# Camera.net
KiCad netlist of a schematic drawn in Altium Designer
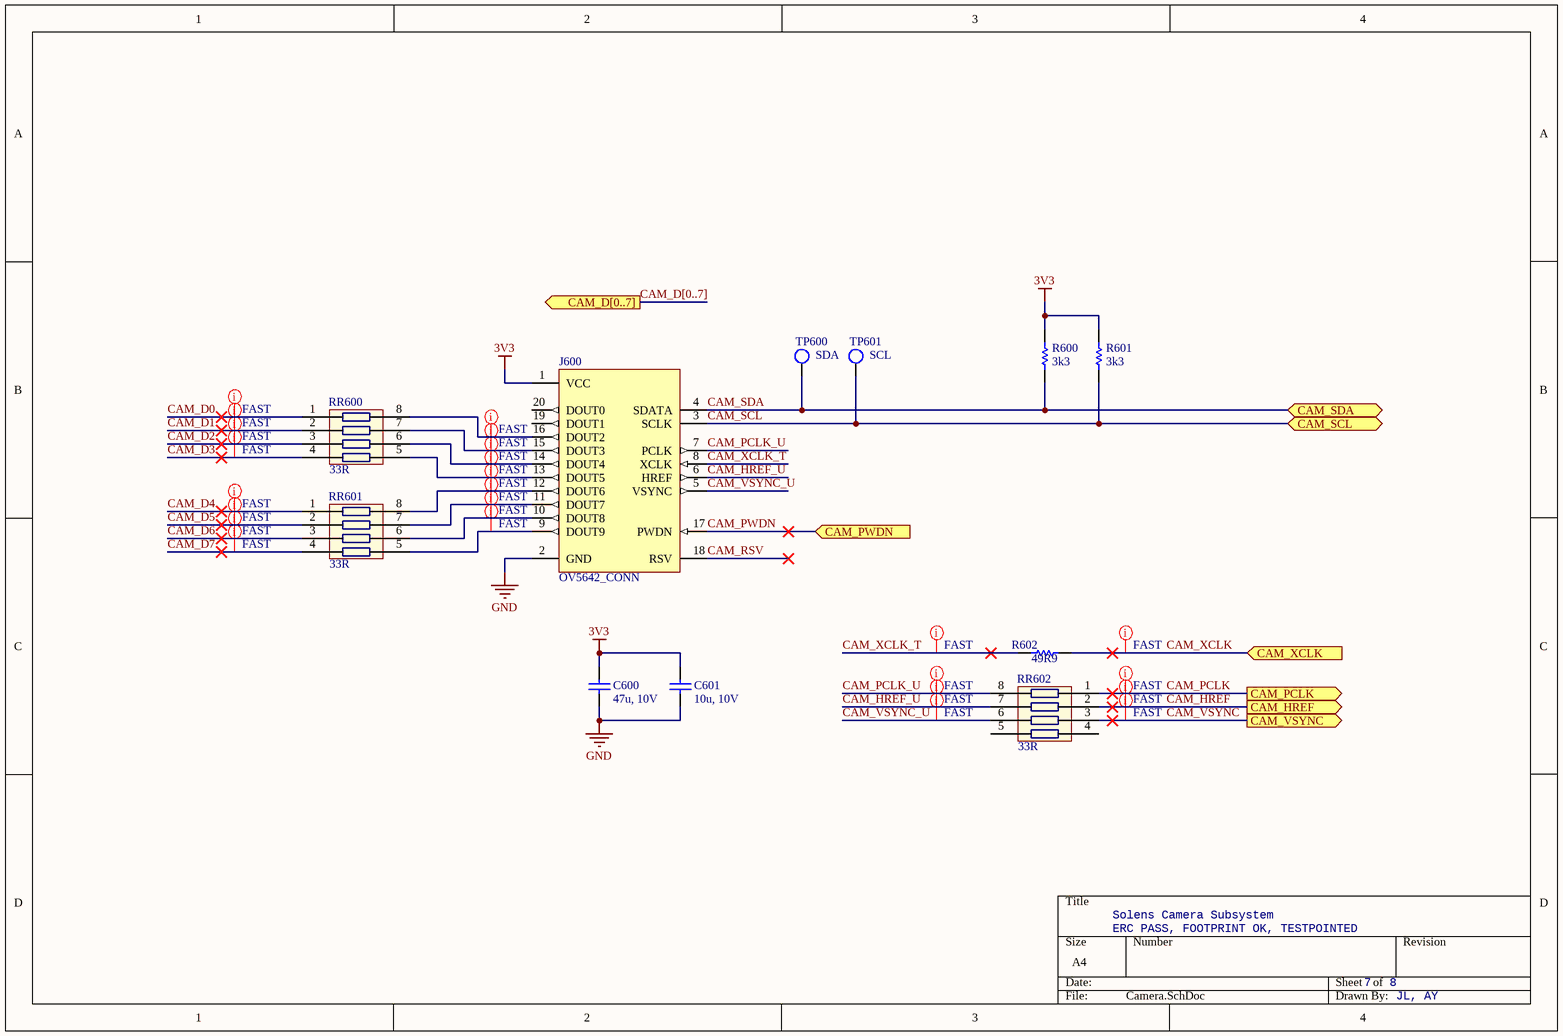
[diagram p0: Camera.SchDoc]

(export (version "E")
  (design (tool "Eeschema 10.0.6"))
  (components
    (comp (ref "C600")
      (value "47u, 10V")
      (footprint "CAP_1206")
      (description "Capacitor")
      (fields (field (name "Comment") "47u, 10V, 1206"))
      (libsource (lib "Miscellaneous Devices") (part "Cap"))
    )
    (comp (ref "C601")
      (value "10u, 10V")
      (footprint "CAP_1206")
      (description "Capacitor")
      (fields (field (name "Comment") "10u, 10V, 1206"))
      (libsource (lib "Miscellaneous Devices") (part "Cap"))
    )
    (comp (ref "J600")
      (value "SOK_2x10_100TH_THT")
      (footprint "OV5642_HDR_2x10")
      (description "20-pin parallel camera connector for OV5642")
      (fields (field (name "FUNCTION") "OV5642_CONN"))
      (libsource (lib "Schlib1") (part "CAMERA_2x10"))
    )
    (comp (ref "R600")
      (value "3k3")
      (footprint "RES_0805")
      (description "Resistor")
      (fields (field (name "Comment") "3k3, 1/8W, 0805"))
      (libsource (lib "Miscellaneous Devices") (part "Res1"))
    )
    (comp (ref "R601")
      (value "3k3")
      (footprint "RES_0805")
      (description "Resistor")
      (fields (field (name "Comment") "3k3, 1/8W, 0805"))
      (libsource (lib "Miscellaneous Devices") (part "Res1"))
    )
    (comp (ref "R602")
      (value "49R9")
      (footprint "RES_0805")
      (description "Resistor")
      (fields (field (name "Comment") "49R9, 1/8W, 0805"))
      (libsource (lib "Miscellaneous Devices") (part "Res1"))
    )
    (comp (ref "RR600")
      (value "33R")
      (footprint "CAC-80P319X150-8M")
      (description "4 element resistor array")
      (fields (field (name "Comment") "CRA6S833CT-ND"))
      (libsource (lib "Schlib1") (part "RES_ARR_4"))
    )
    (comp (ref "RR601")
      (value "33R")
      (footprint "CAC-80P319X150-8M")
      (description "4 element resistor array")
      (fields (field (name "Comment") "CRA6S833CT-ND"))
      (libsource (lib "Schlib1") (part "RES_ARR_4"))
    )
    (comp (ref "RR602")
      (value "33R")
      (footprint "CAC-80P319X150-8M")
      (description "4 element resistor array")
      (fields (field (name "Comment") "CRA6S833CT-ND"))
      (libsource (lib "") (part "RES_ARR_4_1"))
    )
    (comp (ref "TP600")
      (value "TP (DNP)")
      (footprint "TP_SMALL")
      (fields (field (name "VISIBLENETNAME") "SDA"))
      (libsource (lib "Schlib1") (part "TP_SMALL"))
    )
    (comp (ref "TP601")
      (value "TP (DNP)")
      (footprint "TP_SMALL")
      (fields (field (name "VISIBLENETNAME") "SCL"))
      (libsource (lib "Schlib1") (part "TP_SMALL"))
    )
  )
  (nets
    (net (code "1") (name "/CAM_D0") (class "Default")
      (node (ref "RR600") (pin "1") (pinfunction "1A_1") (pintype "passive"))
    )
    (net (code "2") (name "/CAM_D1") (class "Default")
      (node (ref "RR600") (pin "2") (pinfunction "2A_2") (pintype "passive"))
    )
    (net (code "3") (name "/CAM_D2") (class "Default")
      (node (ref "RR600") (pin "3") (pinfunction "3A_3") (pintype "passive"))
    )
    (net (code "4") (name "/CAM_D3") (class "Default")
      (node (ref "RR600") (pin "4") (pinfunction "4A_4") (pintype "passive"))
    )
    (net (code "5") (name "/CAM_D4") (class "Default")
      (node (ref "RR601") (pin "1") (pinfunction "1A_1") (pintype "passive"))
    )
    (net (code "6") (name "/CAM_D5") (class "Default")
      (node (ref "RR601") (pin "2") (pinfunction "2A_2") (pintype "passive"))
    )
    (net (code "7") (name "/CAM_D6") (class "Default")
      (node (ref "RR601") (pin "3") (pinfunction "3A_3") (pintype "passive"))
    )
    (net (code "8") (name "/CAM_D7") (class "Default")
      (node (ref "RR601") (pin "4") (pinfunction "4A_4") (pintype "passive"))
    )
    (net (code "10") (name "/CAM_HREF") (class "Default")
      (node (ref "RR602") (pin "2") (pinfunction "2A_2") (pintype "passive"))
    )
    (net (code "11") (name "/CAM_HREF_U") (class "Default")
      (node (ref "J600") (pin "6") (pinfunction "HREF_6") (pintype "output"))
      (node (ref "RR602") (pin "7") (pinfunction "2B_7") (pintype "passive"))
    )
    (net (code "12") (name "/CAM_PCLK") (class "Default")
      (node (ref "RR602") (pin "1") (pinfunction "1A_1") (pintype "passive"))
    )
    (net (code "13") (name "/CAM_PCLK_U") (class "Default")
      (node (ref "J600") (pin "7") (pinfunction "PCLK_7") (pintype "output"))
      (node (ref "RR602") (pin "8") (pinfunction "1B_8") (pintype "passive"))
    )
    (net (code "14") (name "/CAM_PWDN") (class "Default")
      (node (ref "J600") (pin "17") (pinfunction "PWDN_17") (pintype "input"))
    )
    (net (code "15") (name "/CAM_RSV") (class "Default")
      (node (ref "J600") (pin "18") (pinfunction "RSV_18") (pintype "passive+no_connect"))
    )
    (net (code "16") (name "/CAM_SCL") (class "Default")
      (node (ref "J600") (pin "3") (pinfunction "SCLK_3") (pintype "open_collector"))
      (node (ref "R601") (pin "2") (pinfunction "2_2") (pintype "passive"))
      (node (ref "TP601") (pin "1") (pinfunction "1_1") (pintype "passive"))
    )
    (net (code "17") (name "/CAM_SDA") (class "Default")
      (node (ref "J600") (pin "4") (pinfunction "SDATA_4") (pintype "open_collector"))
      (node (ref "R600") (pin "2") (pinfunction "2_2") (pintype "passive"))
      (node (ref "TP600") (pin "1") (pinfunction "1_1") (pintype "passive"))
    )
    (net (code "18") (name "/CAM_VSYNC") (class "Default")
      (node (ref "RR602") (pin "3") (pinfunction "3A_3") (pintype "passive"))
    )
    (net (code "19") (name "/CAM_VSYNC_U") (class "Default")
      (node (ref "J600") (pin "5") (pinfunction "VSYNC_5") (pintype "output"))
      (node (ref "RR602") (pin "6") (pinfunction "3B_6") (pintype "passive"))
    )
    (net (code "20") (name "/CAM_XCLK") (class "Default")
      (node (ref "R602") (pin "2") (pinfunction "2_2") (pintype "passive"))
    )
    (net (code "21") (name "/CAM_XCLK_T") (class "Default")
      (node (ref "J600") (pin "8") (pinfunction "XCLK_8") (pintype "input"))
      (node (ref "R602") (pin "1") (pinfunction "1_1") (pintype "passive"))
    )
    (net (code "22") (name "3V3") (class "Default")
      (node (ref "C600") (pin "1") (pinfunction "1_1") (pintype "passive"))
      (node (ref "C601") (pin "1") (pinfunction "1_1") (pintype "passive"))
      (node (ref "J600") (pin "1") (pinfunction "VCC_1") (pintype "power_in"))
      (node (ref "R600") (pin "1") (pinfunction "1_1") (pintype "passive"))
      (node (ref "R601") (pin "1") (pinfunction "1_1") (pintype "passive"))
    )
    (net (code "23") (name "GND") (class "Default")
      (node (ref "C600") (pin "2") (pinfunction "2_2") (pintype "passive"))
      (node (ref "C601") (pin "2") (pinfunction "2_2") (pintype "passive"))
      (node (ref "J600") (pin "2") (pinfunction "GND_2") (pintype "power_in"))
    )
    (net (code "24") (name "Net-(J600-DOUT2)") (class "Default")
      (node (ref "J600") (pin "16") (pinfunction "DOUT2_16") (pintype "output"))
      (node (ref "RR600") (pin "8") (pinfunction "1B_8") (pintype "passive"))
    )
    (net (code "25") (name "Net-(J600-DOUT3)") (class "Default")
      (node (ref "J600") (pin "15") (pinfunction "DOUT3_15") (pintype "output"))
      (node (ref "RR600") (pin "7") (pinfunction "2B_7") (pintype "passive"))
    )
    (net (code "26") (name "Net-(J600-DOUT4)") (class "Default")
      (node (ref "J600") (pin "14") (pinfunction "DOUT4_14") (pintype "output"))
      (node (ref "RR600") (pin "6") (pinfunction "3B_6") (pintype "passive"))
    )
    (net (code "27") (name "Net-(J600-DOUT5)") (class "Default")
      (node (ref "J600") (pin "13") (pinfunction "DOUT5_13") (pintype "output"))
      (node (ref "RR600") (pin "5") (pinfunction "4B_5") (pintype "passive"))
    )
    (net (code "28") (name "Net-(J600-DOUT6)") (class "Default")
      (node (ref "J600") (pin "12") (pinfunction "DOUT6_12") (pintype "output"))
      (node (ref "RR601") (pin "8") (pinfunction "1B_8") (pintype "passive"))
    )
    (net (code "29") (name "Net-(J600-DOUT7)") (class "Default")
      (node (ref "J600") (pin "11") (pinfunction "DOUT7_11") (pintype "output"))
      (node (ref "RR601") (pin "7") (pinfunction "2B_7") (pintype "passive"))
    )
    (net (code "30") (name "Net-(J600-DOUT8)") (class "Default")
      (node (ref "J600") (pin "10") (pinfunction "DOUT8_10") (pintype "output"))
      (node (ref "RR601") (pin "6") (pinfunction "3B_6") (pintype "passive"))
    )
    (net (code "31") (name "Net-(J600-DOUT9)") (class "Default")
      (node (ref "J600") (pin "9") (pinfunction "DOUT9_9") (pintype "output"))
      (node (ref "RR601") (pin "5") (pinfunction "4B_5") (pintype "passive"))
    )
    (net (code "32") (name "unconnected-(J600-DOUT0-Pad20)") (class "Default")
      (node (ref "J600") (pin "20") (pinfunction "DOUT0_20") (pintype "output"))
    )
    (net (code "33") (name "unconnected-(J600-DOUT1-Pad19)") (class "Default")
      (node (ref "J600") (pin "19") (pinfunction "DOUT1_19") (pintype "output"))
    )
    (net (code "34") (name "unconnected-(RR602-4A-Pad4)") (class "Default")
      (node (ref "RR602") (pin "4") (pinfunction "4A_4") (pintype "passive"))
    )
    (net (code "35") (name "unconnected-(RR602-4B-Pad5)") (class "Default")
      (node (ref "RR602") (pin "5") (pinfunction "4B_5") (pintype "passive"))
    )
  )
)
